# SCH_Padauk_breakout_sop8_2023-01-24.net
KiCad netlist of a schematic drawn in EasyEDA
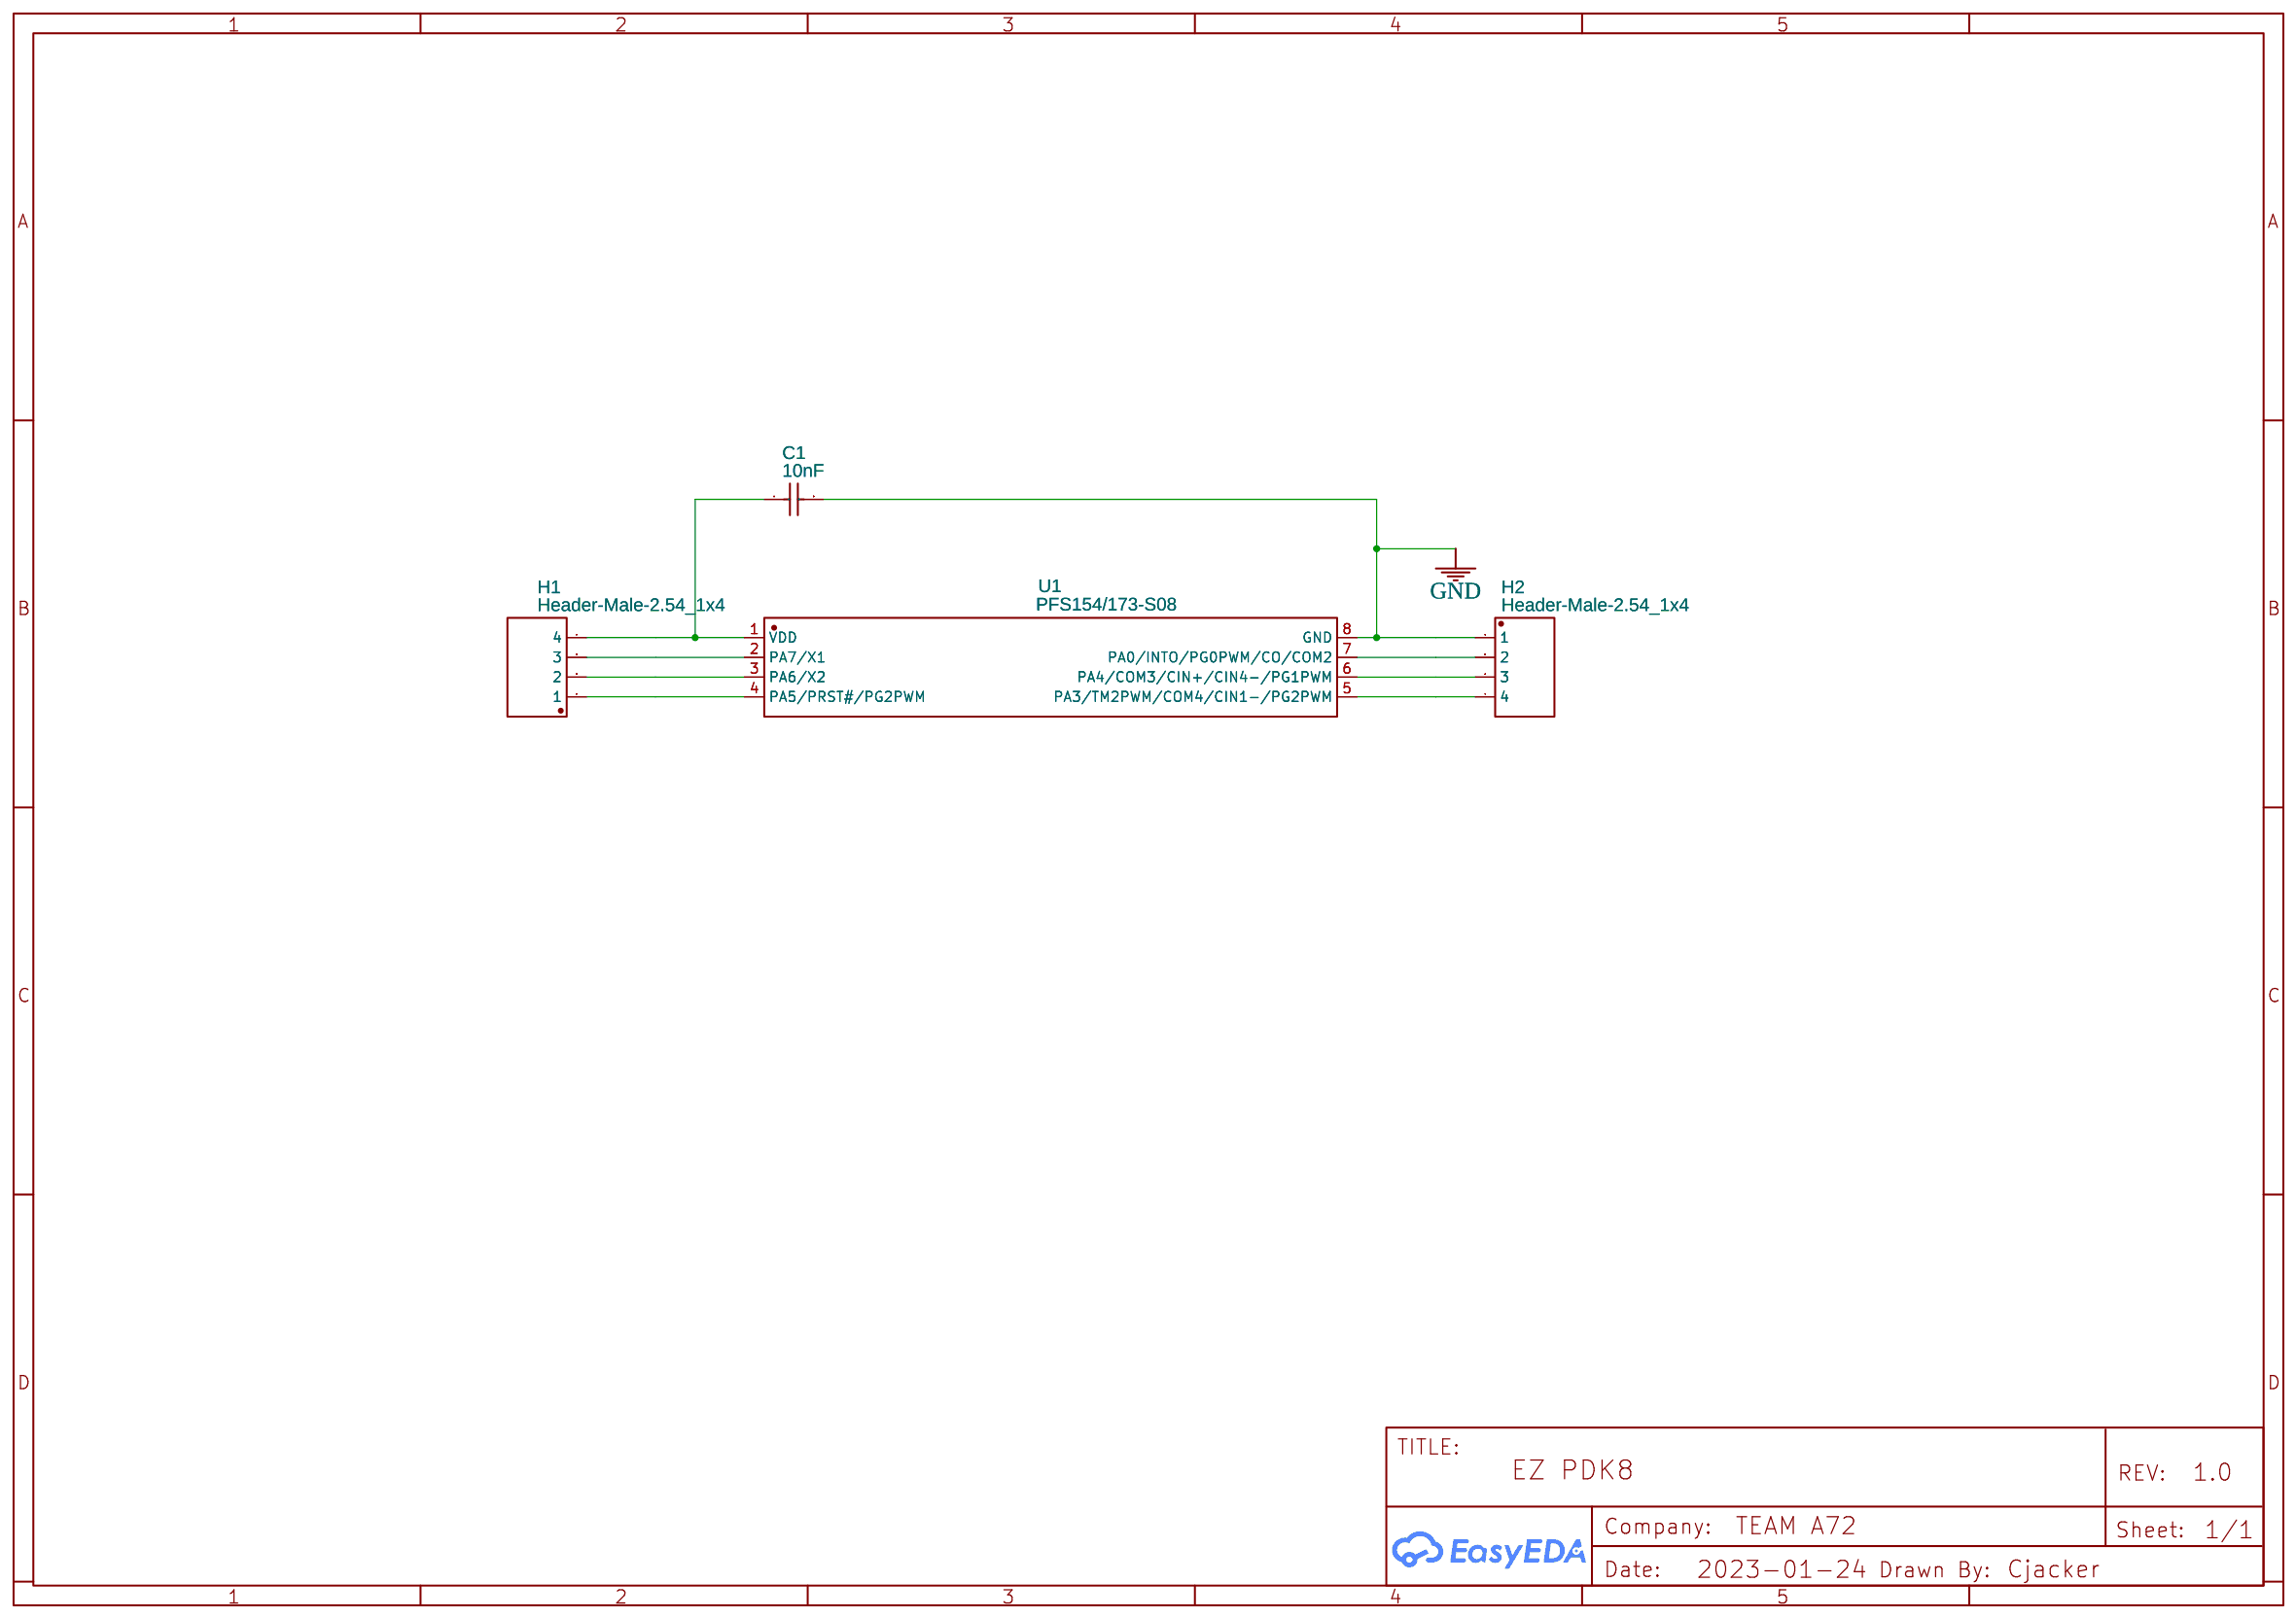
[diagram p0: schematic sheet]

(export (version "E")
  (design (tool "Eeschema 10.0.6"))
  (components
    (comp (ref "C1")
      (value "10nF")
      (fields
        (field (name "BOM_Manufacturer Part") "0805CG103J500NT")
        (field (name "BOM_Supplier Part") "C63849")
      )
      (libsource (lib "") (part "0805CG103J500NT"))
    )
    (comp (ref "H1")
      (value "Header-Male-2.54_1x4")
      (fields
        (field (name "BOM_Manufacturer Part") "210S-1*4P L=11.6MMGold-plated black")
        (field (name "BOM_Supplier Part") "C124378")
      )
      (libsource (lib "") (part "Header-Male-2.54_1x4"))
    )
    (comp (ref "H2")
      (value "Header-Male-2.54_1x4")
      (fields
        (field (name "BOM_Manufacturer Part") "210S-1*4P L=11.6MMGold-plated black")
        (field (name "BOM_Supplier Part") "C124378")
      )
      (libsource (lib "") (part "Header-Male-2.54_1x4_1"))
    )
    (comp (ref "U1")
      (value "PFS154/173-S08")
      (fields
        (field (name "BOM_Manufacturer Part") "PMS154C-S08")
        (field (name "BOM_Supplier Part") "C168657")
      )
      (libsource (lib "") (part "PMS154C-S08"))
    )
  )
  (nets
    (net (code "1") (name "GND") (class "Default")
      (node (ref "C1") (pin "2") (pinfunction "2_2") (pintype "input"))
      (node (ref "H2") (pin "1") (pinfunction "1_1") (pintype "unspecified"))
      (node (ref "U1") (pin "8") (pinfunction "GND_8") (pintype "unspecified"))
    )
    (net (code "2") (name "Net-(U1-PA0{slash}INTO{slash}PG0PWM{slash}CO{slash}COM2)") (class "Default")
      (node (ref "H2") (pin "2") (pinfunction "2_2") (pintype "unspecified"))
      (node (ref "U1") (pin "7") (pinfunction "PA0/INTO/PG0PWM/CO/COM2_7") (pintype "unspecified"))
    )
    (net (code "3") (name "Net-(U1-PA3{slash}TM2PWM{slash}COM4{slash}CIN1-{slash}PG2PWM)") (class "Default")
      (node (ref "H2") (pin "4") (pinfunction "4_4") (pintype "unspecified"))
      (node (ref "U1") (pin "5") (pinfunction "PA3/TM2PWM/COM4/CIN1-/PG2PWM_5") (pintype "unspecified"))
    )
    (net (code "4") (name "Net-(U1-PA4{slash}COM3{slash}CIN+{slash}CIN4-{slash}PG1PWM)") (class "Default")
      (node (ref "H2") (pin "3") (pinfunction "3_3") (pintype "unspecified"))
      (node (ref "U1") (pin "6") (pinfunction "PA4/COM3/CIN+/CIN4-/PG1PWM_6") (pintype "unspecified"))
    )
    (net (code "5") (name "Net-(U1-PA5{slash}PRST#{slash}PG2PWM)") (class "Default")
      (node (ref "H1") (pin "1") (pinfunction "1_1") (pintype "unspecified"))
      (node (ref "U1") (pin "4") (pinfunction "PA5/PRST#/PG2PWM_4") (pintype "unspecified"))
    )
    (net (code "6") (name "Net-(U1-PA6{slash}X2)") (class "Default")
      (node (ref "H1") (pin "2") (pinfunction "2_2") (pintype "unspecified"))
      (node (ref "U1") (pin "3") (pinfunction "PA6/X2_3") (pintype "unspecified"))
    )
    (net (code "7") (name "Net-(U1-PA7{slash}X1)") (class "Default")
      (node (ref "H1") (pin "3") (pinfunction "3_3") (pintype "unspecified"))
      (node (ref "U1") (pin "2") (pinfunction "PA7/X1_2") (pintype "unspecified"))
    )
    (net (code "8") (name "Net-(U1-VDD)") (class "Default")
      (node (ref "C1") (pin "1") (pinfunction "1_1") (pintype "input"))
      (node (ref "H1") (pin "4") (pinfunction "4_4") (pintype "unspecified"))
      (node (ref "U1") (pin "1") (pinfunction "VDD_1") (pintype "unspecified"))
    )
  )
)
